# A-Main.net
KiCad netlist of a schematic drawn in Altium Designer
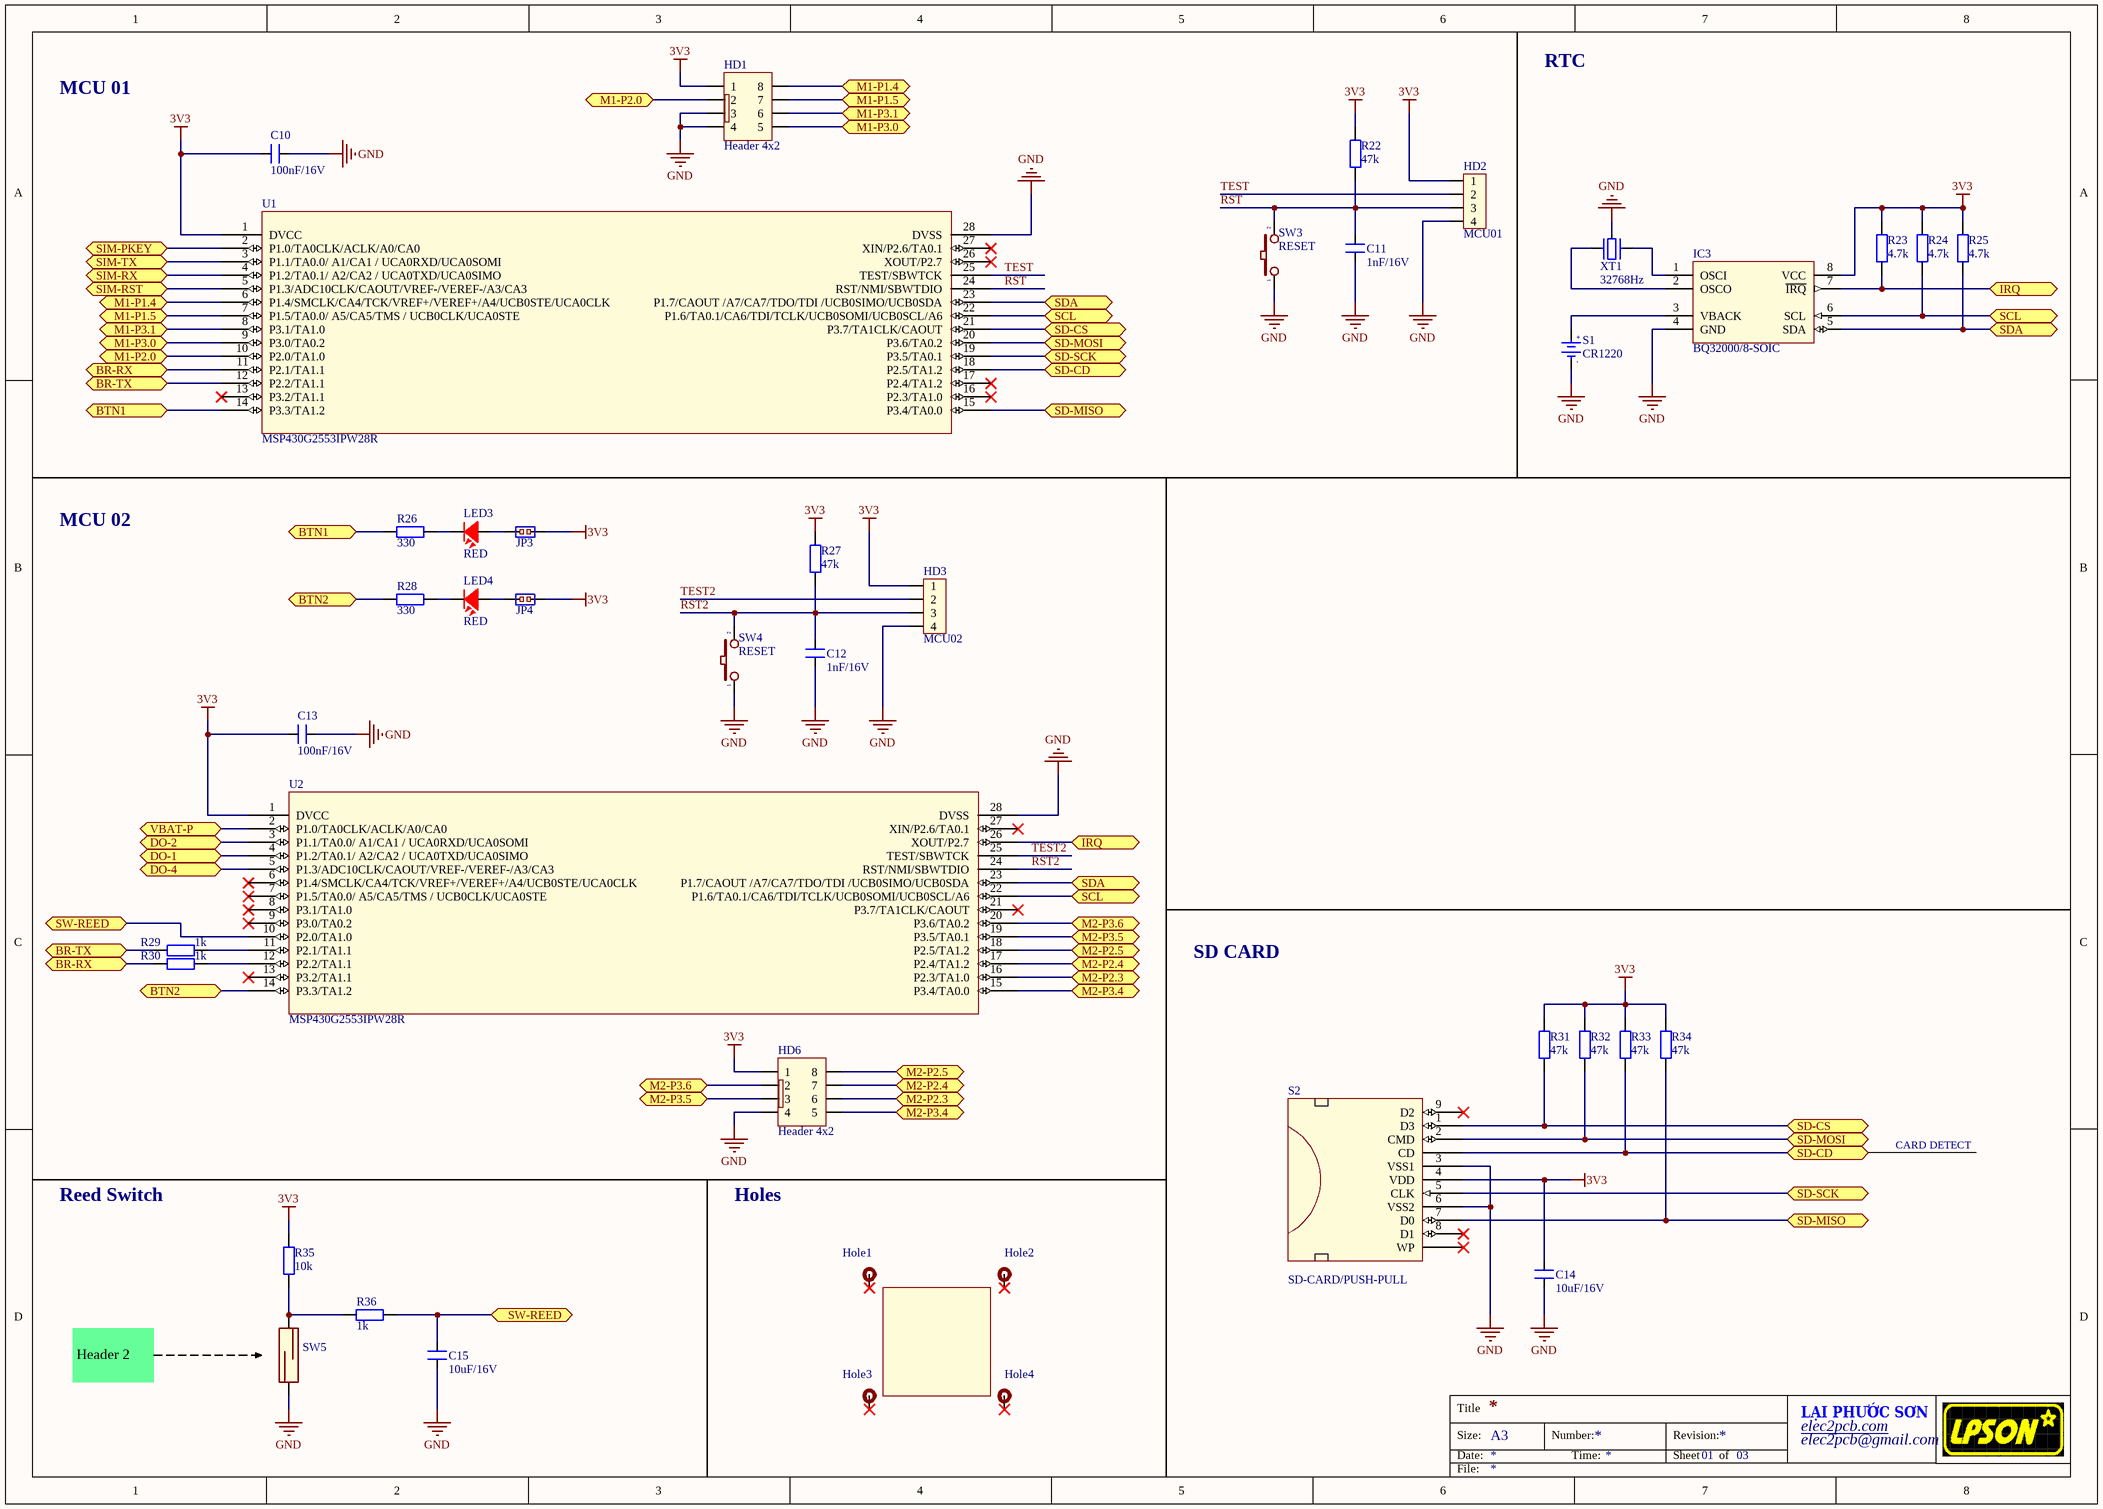
[diagram p0: A-Main.SchDoc]

(export (version "E")
  (design (tool "Eeschema 10.0.6"))
  (components
    (comp (ref "C10")
      (value "100nF/16V")
      (footprint "C0805-2012")
      (description "CAP CER 0.1UF 16V X7R 0805")
      (fields
        (field (name "MANUFACTURER") "Kemet")
        (field (name "MANUFACTURER PART NUMBER") "C0805C104K4RACTU")
      )
      (libsource (lib "Tran Tuan") (part "CAP-CER/100nF/16V/X7R/0805"))
    )
    (comp (ref "C11")
      (value "1nF/16V")
      (footprint "C0603-1608")
      (description "CAP CER 1000PF 16V X7R 0603")
      (fields
        (field (name "MANUFACTURER") "AVX Corporation")
        (field (name "MANUFACTURER PART NUMBER") "0603YC102KAT2A")
      )
      (libsource (lib "Tran Tuan") (part "CAP-CER/1nF/16V/X7R/0603"))
    )
    (comp (ref "C12")
      (value "1nF/16V")
      (footprint "C0603-1608")
      (description "CAP CER 1000PF 16V X7R 0603")
      (fields
        (field (name "MANUFACTURER") "AVX Corporation")
        (field (name "MANUFACTURER PART NUMBER") "0603YC102KAT2A")
      )
      (libsource (lib "Tran Tuan") (part "CAP-CER/1nF/16V/X7R/0603"))
    )
    (comp (ref "C13")
      (value "100nF/16V")
      (footprint "C0805-2012")
      (description "CAP CER 0.1UF 16V X7R 0805")
      (fields
        (field (name "MANUFACTURER") "Kemet")
        (field (name "MANUFACTURER PART NUMBER") "C0805C104K4RACTU")
      )
      (libsource (lib "Tran Tuan") (part "CAP-CER/100nF/16V/X7R/0805"))
    )
    (comp (ref "C14")
      (value "10uF/16V")
      (footprint "C0805-2012")
      (description "CAP CER 10UF 16V X5R 0805")
      (fields
        (field (name "MANUFACTURER") "Murata Electronics North America")
        (field (name "MANUFACTURER PART NUMBER") "GRM21BR61C106KE15L")
      )
      (libsource (lib "Tran Tuan") (part "CAP-CER/10UF/16V/X5R/0805"))
    )
    (comp (ref "C15")
      (value "10uF/16V")
      (footprint "C0805-2012")
      (description "CAP CER 10UF 16V X5R 0805")
      (fields
        (field (name "MANUFACTURER") "Murata Electronics North America")
        (field (name "MANUFACTURER PART NUMBER") "GRM21BR61C106KE15L")
      )
      (libsource (lib "Tran Tuan") (part "CAP-CER/10UF/16V/X5R/0805"))
    )
    (comp (ref "HD1")
      (value "Header 4x2")
      (footprint "HeaderSP_4x2")
      (description "HEADER, 4X2, 2.54MM, MALE")
      (libsource (lib "Tran Tuan") (part "HED-4X2/MALE/2.54MM-B"))
    )
    (comp (ref "HD2")
      (value "MCU01")
      (footprint "Header_4")
      (description "Header 4")
      (libsource (lib "Tran Tuan") (part "Hed4"))
    )
    (comp (ref "HD3")
      (value "MCU02")
      (footprint "Header_4")
      (description "Header 4")
      (libsource (lib "Tran Tuan") (part "Hed4"))
    )
    (comp (ref "HD6")
      (value "Header 4x2")
      (footprint "HeaderSP_4x2")
      (description "HEADER, 4X2, 2.54MM, MALE")
      (libsource (lib "Tran Tuan") (part "HED-4X2/MALE/2.54MM-B"))
    )
    (comp (ref "Hole1")
      (value "Pad Big")
      (footprint "Screw 3.0")
      (libsource (lib "Tran Tuan") (part "Pad_Big"))
    )
    (comp (ref "Hole2")
      (value "Pad Big")
      (footprint "Screw 3.0")
      (libsource (lib "Tran Tuan") (part "Pad_Big"))
    )
    (comp (ref "Hole3")
      (value "Pad Big")
      (footprint "Screw 3.0")
      (libsource (lib "Tran Tuan") (part "Pad_Big"))
    )
    (comp (ref "Hole4")
      (value "Pad Big")
      (footprint "Screw 3.0")
      (libsource (lib "Tran Tuan") (part "Pad_Big"))
    )
    (comp (ref "IC3")
      (value "BQ32000/8-SOIC")
      (footprint "RTC-BQ32000")
      (description "IC RTC CLK/CALENDAR I2C 8-SOIC")
      (fields
        (field (name "MANUFACTURER") "Texas Instruments")
        (field (name "MANUFACTURER PART NUMBER") "BQ32000DR")
      )
      (libsource (lib "Tran Tuan") (part "BQ32000/8-SOIC"))
    )
    (comp (ref "JP3")
      (value "JP2-ShortingJumper")
      (footprint "Header_2")
      (description "2.54mm 2-Pin Shorting Jumper")
      (libsource (lib "Tran Tuan") (part "JP2-ShortingJumper"))
    )
    (comp (ref "JP4")
      (value "JP2-ShortingJumper")
      (footprint "Header_2")
      (description "2.54mm 2-Pin Shorting Jumper")
      (libsource (lib "Tran Tuan") (part "JP2-ShortingJumper"))
    )
    (comp (ref "LED3")
      (value "RED")
      (footprint "Led 0805R")
      (description "LED RED CLEAR 0805 SMD")
      (fields
        (field (name "MANUFACTURER") "Lite-On Inc.")
        (field (name "MANUFACTURER PART NUMBER") "LTST-C171KRKT")
      )
      (libsource (lib "Tran Tuan") (part "LED-RED/CLEAR/0805"))
    )
    (comp (ref "LED4")
      (value "RED")
      (footprint "Led 0805R")
      (description "LED RED CLEAR 0805 SMD")
      (fields
        (field (name "MANUFACTURER") "Lite-On Inc.")
        (field (name "MANUFACTURER PART NUMBER") "LTST-C171KRKT")
      )
      (libsource (lib "Tran Tuan") (part "LED-RED/CLEAR/0805"))
    )
    (comp (ref "R22")
      (value "~")
      (footprint "RESC2012(0805)")
      (description "RES SMD 47K OHM 5% 1/8W 0805")
      (fields
        (field (name "MANUFACTURER") "Yageo")
        (field (name "MANUFACTURER PART NUMBER") "RC0805JR-0747KL")
        (field (name "RESISTANCE (OHMS)") "47k")
      )
      (libsource (lib "") (part "RES-0805/±5%_1"))
    )
    (comp (ref "R23")
      (value "~")
      (footprint "RESC2012(0805)")
      (description "RES SMD 4.7K OHM 5% 1/8W 0805")
      (fields
        (field (name "MANUFACTURER") "Yageo")
        (field (name "MANUFACTURER PART NUMBER") "RC0805JR-074K7L")
        (field (name "RESISTANCE (OHMS)") "4.7k")
      )
      (libsource (lib "") (part "RES-0805/±5%_1"))
    )
    (comp (ref "R24")
      (value "~")
      (footprint "RESC2012(0805)")
      (description "RES SMD 4.7K OHM 5% 1/8W 0805")
      (fields
        (field (name "MANUFACTURER") "Yageo")
        (field (name "MANUFACTURER PART NUMBER") "RC0805JR-074K7L")
        (field (name "RESISTANCE (OHMS)") "4.7k")
      )
      (libsource (lib "") (part "RES-0805/±5%_1"))
    )
    (comp (ref "R25")
      (value "~")
      (footprint "RESC2012(0805)")
      (description "RES SMD 4.7K OHM 5% 1/8W 0805")
      (fields
        (field (name "MANUFACTURER") "Yageo")
        (field (name "MANUFACTURER PART NUMBER") "RC0805JR-074K7L")
        (field (name "RESISTANCE (OHMS)") "4.7k")
      )
      (libsource (lib "") (part "RES-0805/±5%_1"))
    )
    (comp (ref "R26")
      (value "~")
      (footprint "RESC2012(0805)")
      (description "RES SMD 330 OHM 5% 1/8W 0805")
      (fields
        (field (name "MANUFACTURER") "Yageo")
        (field (name "MANUFACTURER PART NUMBER") "RC0805JR-07330RL")
        (field (name "RESISTANCE (OHMS)") "330")
      )
      (libsource (lib "Tran Tuan") (part "RES-0805/±5%"))
    )
    (comp (ref "R27")
      (value "~")
      (footprint "RESC2012(0805)")
      (description "RES SMD 47K OHM 5% 1/8W 0805")
      (fields
        (field (name "MANUFACTURER") "Yageo")
        (field (name "MANUFACTURER PART NUMBER") "RC0805JR-0747KL")
        (field (name "RESISTANCE (OHMS)") "47k")
      )
      (libsource (lib "") (part "RES-0805/±5%_1"))
    )
    (comp (ref "R28")
      (value "~")
      (footprint "RESC2012(0805)")
      (description "RES SMD 330 OHM 5% 1/8W 0805")
      (fields
        (field (name "MANUFACTURER") "Yageo")
        (field (name "MANUFACTURER PART NUMBER") "RC0805JR-07330RL")
        (field (name "RESISTANCE (OHMS)") "330")
      )
      (libsource (lib "Tran Tuan") (part "RES-0805/±5%"))
    )
    (comp (ref "R29")
      (value "~")
      (footprint "RESC2012(0805)")
      (description "RES SMD 1K OHM 5% 1/8W 0805")
      (fields
        (field (name "MANUFACTURER") "Yageo")
        (field (name "MANUFACTURER PART NUMBER") "RC0805JR-071KL")
        (field (name "RESISTANCE (OHMS)") "1k")
      )
      (libsource (lib "Tran Tuan") (part "RES-0805/±5%"))
    )
    (comp (ref "R30")
      (value "~")
      (footprint "RESC2012(0805)")
      (description "RES SMD 1K OHM 5% 1/8W 0805")
      (fields
        (field (name "MANUFACTURER") "Yageo")
        (field (name "MANUFACTURER PART NUMBER") "RC0805JR-071KL")
        (field (name "RESISTANCE (OHMS)") "1k")
      )
      (libsource (lib "Tran Tuan") (part "RES-0805/±5%"))
    )
    (comp (ref "R31")
      (value "~")
      (footprint "RESC2012(0805)")
      (description "RES SMD 47K OHM 5% 1/8W 0805")
      (fields
        (field (name "MANUFACTURER") "Yageo")
        (field (name "MANUFACTURER PART NUMBER") "RC0805JR-0747KL")
        (field (name "RESISTANCE (OHMS)") "47k")
      )
      (libsource (lib "") (part "RES-0805/±5%_1"))
    )
    (comp (ref "R32")
      (value "~")
      (footprint "RESC2012(0805)")
      (description "RES SMD 47K OHM 5% 1/8W 0805")
      (fields
        (field (name "MANUFACTURER") "Yageo")
        (field (name "MANUFACTURER PART NUMBER") "RC0805JR-0747KL")
        (field (name "RESISTANCE (OHMS)") "47k")
      )
      (libsource (lib "") (part "RES-0805/±5%_1"))
    )
    (comp (ref "R33")
      (value "~")
      (footprint "RESC2012(0805)")
      (description "RES SMD 47K OHM 5% 1/8W 0805")
      (fields
        (field (name "MANUFACTURER") "Yageo")
        (field (name "MANUFACTURER PART NUMBER") "RC0805JR-0747KL")
        (field (name "RESISTANCE (OHMS)") "47k")
      )
      (libsource (lib "") (part "RES-0805/±5%_1"))
    )
    (comp (ref "R34")
      (value "~")
      (footprint "RESC2012(0805)")
      (description "RES SMD 47K OHM 5% 1/8W 0805")
      (fields
        (field (name "MANUFACTURER") "Yageo")
        (field (name "MANUFACTURER PART NUMBER") "RC0805JR-0747KL")
        (field (name "RESISTANCE (OHMS)") "47k")
      )
      (libsource (lib "") (part "RES-0805/±5%_1"))
    )
    (comp (ref "R35")
      (value "~")
      (footprint "RESC2012(0805)")
      (description "RES SMD 10K OHM 5% 1/8W 0805")
      (fields
        (field (name "MANUFACTURER") "Yageo")
        (field (name "MANUFACTURER PART NUMBER") "RC0805JR-0710KL")
        (field (name "RESISTANCE (OHMS)") "10k")
      )
      (libsource (lib "") (part "RES-0805/±5%_2"))
    )
    (comp (ref "R36")
      (value "~")
      (footprint "RESC2012(0805)")
      (description "RES SMD 1K OHM 5% 1/8W 0805")
      (fields
        (field (name "MANUFACTURER") "Yageo")
        (field (name "MANUFACTURER PART NUMBER") "RC0805JR-071KL")
        (field (name "RESISTANCE (OHMS)") "1k")
      )
      (libsource (lib "Tran Tuan") (part "RES-0805/±5%"))
    )
    (comp (ref "S1")
      (value "CR1220")
      (footprint "Socket-PIN-BC501SM-TR")
      (description "CR1220 Battery Holder SMD")
      (fields (field (name "Comment") "BAT-HOLDER/CR1220/TME"))
      (libsource (lib "Tran Tuan") (part "BAT-HOLDER/CR1220/TME"))
    )
    (comp (ref "S2")
      (value "SD-CARD/PUSH-PULL")
      (footprint "SD-CARD")
      (description "CONN SD CARD PUSH-PUSH R/A SMD")
      (fields
        (field (name "MANUFACTURER") "Amphenol Commercial Products")
        (field (name "MANUFACTURER PART NUMBER") "101-00313-68-02")
      )
      (libsource (lib "Tran Tuan") (part "SD-CARD/PUSH-PULL"))
    )
    (comp (ref "SW3")
      (value "RESET")
      (footprint "BTN-EVQ-11A04M")
      (description "SWITCH TACTILE SPST-NO 0.02A 15V")
      (fields
        (field (name "MANUFACTURER") "Panasonic Electronic Components")
        (field (name "MANUFACTURER PART NUMBER") "EVQ-11A04M")
      )
      (libsource (lib "Tran Tuan") (part "SW2-PUSH/SPST/NO"))
    )
    (comp (ref "SW4")
      (value "RESET")
      (footprint "BTN-EVQ-11A04M")
      (description "SWITCH TACTILE SPST-NO 0.02A 15V")
      (fields
        (field (name "MANUFACTURER") "Panasonic Electronic Components")
        (field (name "MANUFACTURER PART NUMBER") "EVQ-11A04M")
      )
      (libsource (lib "Tran Tuan") (part "SW2-PUSH/SPST/NO"))
    )
    (comp (ref "SW5")
      (value "SW-REED/SPST/NO/350mA")
      (footprint "SWITCH-SDSM")
      (description "SWITCH REED SPST-NO 350MA 140V")
      (fields
        (field (name "MANUFACTURER") "Littelfuse Inc.")
        (field (name "MANUFACTURER PART NUMBER") "MDSM-4R-12-18")
      )
      (libsource (lib "Tran Tuan") (part "SW-REED/SPST/NO/350mA"))
    )
    (comp (ref "U1")
      (value "MSP430G2553IPW28R")
      (footprint "MSP430G2253IPW28R")
      (description "IC MCU 16BIT 16KB FLASH 28TSSOP")
      (fields (field (name "MANUFACTURER") "Texas Instruments"))
      (libsource (lib "Tran Tuan") (part "MSP430G2553IPW28R"))
    )
    (comp (ref "U2")
      (value "MSP430G2553IPW28R")
      (footprint "MSP430G2253IPW28R")
      (description "IC MCU 16BIT 16KB FLASH 28TSSOP")
      (fields (field (name "MANUFACTURER") "Texas Instruments"))
      (libsource (lib "Tran Tuan") (part "MSP430G2553IPW28R"))
    )
    (comp (ref "XT1")
      (value "32768Hz")
      (footprint "CR_32768")
      (description "CRYSTAL 32.7680KHZ 12.5PF T/H")
      (fields
        (field (name "MANUFACTURER") "Citizen Finedevice Co Ltd")
        (field (name "MANUFACTURER PART NUMBER") "CFS206-32.768KDZF-UB")
      )
      (libsource (lib "Tran Tuan") (part "XT-32768HZ/RADIAL"))
    )
  )
  (nets
    (net (code "1") (name "/BR-RX") (class "Default")
      (node (ref "R30") (pin "2") (pinfunction "2_2") (pintype "passive"))
      (node (ref "U1") (pin "11") (pinfunction "P2.1/TA1.1_11") (pintype "bidirectional"))
    )
    (net (code "2") (name "/BR-TX") (class "Default")
      (node (ref "R29") (pin "2") (pinfunction "2_2") (pintype "passive"))
      (node (ref "U1") (pin "12") (pinfunction "P2.2/TA1.1_12") (pintype "bidirectional"))
    )
    (net (code "3") (name "/BTN1") (class "Default")
      (node (ref "R26") (pin "2") (pinfunction "2_2") (pintype "passive"))
      (node (ref "U1") (pin "14") (pinfunction "P3.3/TA1.2_14") (pintype "bidirectional"))
    )
    (net (code "4") (name "/BTN2") (class "Default")
      (node (ref "R28") (pin "2") (pinfunction "2_2") (pintype "passive"))
      (node (ref "U2") (pin "14") (pinfunction "P3.3/TA1.2_14") (pintype "bidirectional"))
    )
    (net (code "5") (name "/DO-1") (class "Default")
      (node (ref "U2") (pin "4") (pinfunction "P1.2/TA0.1/_A2/CA2_/_UCA0TXD/UCA0SIMO_4") (pintype "bidirectional"))
    )
    (net (code "6") (name "/DO-2") (class "Default")
      (node (ref "U2") (pin "3") (pinfunction "P1.1/TA0.0/_A1/CA1_/_UCA0RXD/UCA0SOMI_3") (pintype "bidirectional"))
    )
    (net (code "7") (name "/DO-4") (class "Default")
      (node (ref "U2") (pin "5") (pinfunction "P1.3/ADC10CLK/CAOUT/VREF-/VEREF-/A3/CA3_5") (pintype "bidirectional"))
    )
    (net (code "8") (name "/IRQ") (class "Default")
      (node (ref "IC3") (pin "7") (pinfunction "~{IRQ}_7") (pintype "output"))
      (node (ref "R23") (pin "1") (pinfunction "1_1") (pintype "passive"))
      (node (ref "U2") (pin "26") (pinfunction "XOUT/P2.7_26") (pintype "bidirectional"))
    )
    (net (code "9") (name "/M1-P1.4") (class "Default")
      (node (ref "HD1") (pin "8") (pinfunction "8_8") (pintype "passive"))
      (node (ref "U1") (pin "6") (pinfunction "P1.4/SMCLK/CA4/TCK/VREF+/VEREF+/A4/UCB0STE/UCA0CLK_6") (pintype "bidirectional"))
    )
    (net (code "10") (name "/M1-P1.5") (class "Default")
      (node (ref "HD1") (pin "7") (pinfunction "7_7") (pintype "passive"))
      (node (ref "U1") (pin "7") (pinfunction "P1.5/TA0.0/_A5/CA5/TMS_/_UCB0CLK/UCA0STE_7") (pintype "bidirectional"))
    )
    (net (code "11") (name "/M1-P2.0") (class "Default")
      (node (ref "HD1") (pin "2") (pinfunction "2_2") (pintype "passive"))
      (node (ref "U1") (pin "10") (pinfunction "P2.0/TA1.0_10") (pintype "bidirectional"))
    )
    (net (code "12") (name "/M1-P3.0") (class "Default")
      (node (ref "HD1") (pin "5") (pinfunction "5_5") (pintype "passive"))
      (node (ref "U1") (pin "9") (pinfunction "P3.0/TA0.2_9") (pintype "bidirectional"))
    )
    (net (code "13") (name "/M1-P3.1") (class "Default")
      (node (ref "HD1") (pin "6") (pinfunction "6_6") (pintype "passive"))
      (node (ref "U1") (pin "8") (pinfunction "P3.1/TA1.0_8") (pintype "bidirectional"))
    )
    (net (code "14") (name "/M2-P2.3") (class "Default")
      (node (ref "HD6") (pin "6") (pinfunction "6_6") (pintype "passive"))
      (node (ref "U2") (pin "16") (pinfunction "P2.3/TA1.0_16") (pintype "bidirectional"))
    )
    (net (code "15") (name "/M2-P2.4") (class "Default")
      (node (ref "HD6") (pin "7") (pinfunction "7_7") (pintype "passive"))
      (node (ref "U2") (pin "17") (pinfunction "P2.4/TA1.2_17") (pintype "bidirectional"))
    )
    (net (code "16") (name "/M2-P2.5") (class "Default")
      (node (ref "HD6") (pin "8") (pinfunction "8_8") (pintype "passive"))
      (node (ref "U2") (pin "18") (pinfunction "P2.5/TA1.2_18") (pintype "bidirectional"))
    )
    (net (code "17") (name "/M2-P3.4") (class "Default")
      (node (ref "HD6") (pin "5") (pinfunction "5_5") (pintype "passive"))
      (node (ref "U2") (pin "15") (pinfunction "P3.4/TA0.0_15") (pintype "bidirectional"))
    )
    (net (code "18") (name "/M2-P3.5") (class "Default")
      (node (ref "HD6") (pin "3") (pinfunction "3_3") (pintype "passive"))
      (node (ref "U2") (pin "19") (pinfunction "P3.5/TA0.1_19") (pintype "bidirectional"))
    )
    (net (code "19") (name "/M2-P3.6") (class "Default")
      (node (ref "HD6") (pin "2") (pinfunction "2_2") (pintype "passive"))
      (node (ref "U2") (pin "20") (pinfunction "P3.6/TA0.2_20") (pintype "bidirectional"))
    )
    (net (code "20") (name "/RST") (class "Default")
      (node (ref "C11") (pin "1") (pinfunction "1_1") (pintype "passive"))
      (node (ref "HD2") (pin "3") (pinfunction "3_3") (pintype "passive"))
      (node (ref "R22") (pin "1") (pinfunction "1_1") (pintype "passive"))
      (node (ref "SW3") (pin "2") (pinfunction "2_2") (pintype "passive"))
      (node (ref "U1") (pin "24") (pinfunction "RST/NMI/SBWTDIO_24") (pintype "passive"))
    )
    (net (code "21") (name "/RST2") (class "Default")
      (node (ref "C12") (pin "1") (pinfunction "1_1") (pintype "passive"))
      (node (ref "HD3") (pin "3") (pinfunction "3_3") (pintype "passive"))
      (node (ref "R27") (pin "1") (pinfunction "1_1") (pintype "passive"))
      (node (ref "SW4") (pin "2") (pinfunction "2_2") (pintype "passive"))
      (node (ref "U2") (pin "24") (pinfunction "RST/NMI/SBWTDIO_24") (pintype "passive"))
    )
    (net (code "22") (name "/SCL") (class "Default")
      (node (ref "IC3") (pin "6") (pinfunction "SCL_6") (pintype "input"))
      (node (ref "R24") (pin "1") (pinfunction "1_1") (pintype "passive"))
      (node (ref "U1") (pin "22") (pinfunction "P1.6/TA0.1/CA6/TDI/TCLK/UCB0SOMI/UCB0SCL/A6_22") (pintype "bidirectional"))
      (node (ref "U2") (pin "22") (pinfunction "P1.6/TA0.1/CA6/TDI/TCLK/UCB0SOMI/UCB0SCL/A6_22") (pintype "bidirectional"))
    )
    (net (code "23") (name "/SD-CD") (class "Default")
      (node (ref "R33") (pin "1") (pinfunction "1_1") (pintype "passive"))
      (node (ref "S2") (pin "CD") (pinfunction "CD_CD") (pintype "passive"))
      (node (ref "U1") (pin "18") (pinfunction "P2.5/TA1.2_18") (pintype "bidirectional"))
    )
    (net (code "24") (name "/SD-CS") (class "Default")
      (node (ref "R31") (pin "1") (pinfunction "1_1") (pintype "passive"))
      (node (ref "S2") (pin "1") (pinfunction "D3_1") (pintype "bidirectional"))
      (node (ref "U1") (pin "21") (pinfunction "P3.7/TA1CLK/CAOUT_21") (pintype "bidirectional"))
    )
    (net (code "25") (name "/SD-MISO") (class "Default")
      (node (ref "R34") (pin "1") (pinfunction "1_1") (pintype "passive"))
      (node (ref "S2") (pin "7") (pinfunction "D0_7") (pintype "bidirectional"))
      (node (ref "U1") (pin "15") (pinfunction "P3.4/TA0.0_15") (pintype "bidirectional"))
    )
    (net (code "26") (name "/SD-MOSI") (class "Default")
      (node (ref "R32") (pin "1") (pinfunction "1_1") (pintype "passive"))
      (node (ref "S2") (pin "2") (pinfunction "CMD_2") (pintype "bidirectional"))
      (node (ref "U1") (pin "20") (pinfunction "P3.6/TA0.2_20") (pintype "bidirectional"))
    )
    (net (code "27") (name "/SD-SCK") (class "Default")
      (node (ref "S2") (pin "5") (pinfunction "CLK_5") (pintype "input"))
      (node (ref "U1") (pin "19") (pinfunction "P3.5/TA0.1_19") (pintype "bidirectional"))
    )
    (net (code "28") (name "/SDA") (class "Default")
      (node (ref "IC3") (pin "5") (pinfunction "SDA_5") (pintype "bidirectional"))
      (node (ref "R25") (pin "1") (pinfunction "1_1") (pintype "passive"))
      (node (ref "U1") (pin "23") (pinfunction "P1.7/CAOUT_/A7/CA7/TDO/TDI_/UCB0SIMO/UCB0SDA_23") (pintype "bidirectional"))
      (node (ref "U2") (pin "23") (pinfunction "P1.7/CAOUT_/A7/CA7/TDO/TDI_/UCB0SIMO/UCB0SDA_23") (pintype "bidirectional"))
    )
    (net (code "29") (name "/SIM-PKEY") (class "Default")
      (node (ref "U1") (pin "2") (pinfunction "P1.0/TA0CLK/ACLK/A0/CA0_2") (pintype "bidirectional"))
    )
    (net (code "30") (name "/SIM-RST") (class "Default")
      (node (ref "U1") (pin "5") (pinfunction "P1.3/ADC10CLK/CAOUT/VREF-/VEREF-/A3/CA3_5") (pintype "bidirectional"))
    )
    (net (code "31") (name "/SIM-RX") (class "Default")
      (node (ref "U1") (pin "4") (pinfunction "P1.2/TA0.1/_A2/CA2_/_UCA0TXD/UCA0SIMO_4") (pintype "bidirectional"))
    )
    (net (code "32") (name "/SIM-TX") (class "Default")
      (node (ref "U1") (pin "3") (pinfunction "P1.1/TA0.0/_A1/CA1_/_UCA0RXD/UCA0SOMI_3") (pintype "bidirectional"))
    )
    (net (code "33") (name "/SW-REED") (class "Default")
      (node (ref "C15") (pin "1") (pinfunction "1_1") (pintype "passive"))
      (node (ref "R36") (pin "1") (pinfunction "1_1") (pintype "passive"))
      (node (ref "U2") (pin "10") (pinfunction "P2.0/TA1.0_10") (pintype "bidirectional"))
    )
    (net (code "34") (name "/TEST") (class "Default")
      (node (ref "HD2") (pin "2") (pinfunction "2_2") (pintype "passive"))
      (node (ref "U1") (pin "25") (pinfunction "TEST/SBWTCK_25") (pintype "passive"))
    )
    (net (code "35") (name "/TEST2") (class "Default")
      (node (ref "HD3") (pin "2") (pinfunction "2_2") (pintype "passive"))
      (node (ref "U2") (pin "25") (pinfunction "TEST/SBWTCK_25") (pintype "passive"))
    )
    (net (code "36") (name "/VBAT-P") (class "Default")
      (node (ref "U2") (pin "2") (pinfunction "P1.0/TA0CLK/ACLK/A0/CA0_2") (pintype "bidirectional"))
    )
    (net (code "37") (name "3V3") (class "Default")
      (node (ref "C10") (pin "1") (pinfunction "1_1") (pintype "passive"))
      (node (ref "C13") (pin "1") (pinfunction "1_1") (pintype "passive"))
      (node (ref "C14") (pin "1") (pinfunction "1_1") (pintype "passive"))
      (node (ref "HD1") (pin "1") (pinfunction "1_1") (pintype "passive"))
      (node (ref "HD2") (pin "1") (pinfunction "1_1") (pintype "passive"))
      (node (ref "HD3") (pin "1") (pinfunction "1_1") (pintype "passive"))
      (node (ref "HD6") (pin "1") (pinfunction "1_1") (pintype "passive"))
      (node (ref "IC3") (pin "8") (pinfunction "VCC_8") (pintype "power_in"))
      (node (ref "JP3") (pin "2") (pinfunction "2_2") (pintype "passive"))
      (node (ref "JP4") (pin "2") (pinfunction "2_2") (pintype "passive"))
      (node (ref "R22") (pin "2") (pinfunction "2_2") (pintype "passive"))
      (node (ref "R23") (pin "2") (pinfunction "2_2") (pintype "passive"))
      (node (ref "R24") (pin "2") (pinfunction "2_2") (pintype "passive"))
      (node (ref "R25") (pin "2") (pinfunction "2_2") (pintype "passive"))
      (node (ref "R27") (pin "2") (pinfunction "2_2") (pintype "passive"))
      (node (ref "R31") (pin "2") (pinfunction "2_2") (pintype "passive"))
      (node (ref "R32") (pin "2") (pinfunction "2_2") (pintype "passive"))
      (node (ref "R33") (pin "2") (pinfunction "2_2") (pintype "passive"))
      (node (ref "R34") (pin "2") (pinfunction "2_2") (pintype "passive"))
      (node (ref "R35") (pin "1") (pinfunction "1_1") (pintype "passive"))
      (node (ref "S2") (pin "4") (pinfunction "VDD_4") (pintype "power_in"))
      (node (ref "U1") (pin "1") (pinfunction "DVCC_1") (pintype "power_in"))
      (node (ref "U2") (pin "1") (pinfunction "DVCC_1") (pintype "power_in"))
    )
    (net (code "38") (name "GND") (class "Default")
      (node (ref "C10") (pin "2") (pinfunction "2_2") (pintype "passive"))
      (node (ref "C11") (pin "2") (pinfunction "2_2") (pintype "passive"))
      (node (ref "C12") (pin "2") (pinfunction "2_2") (pintype "passive"))
      (node (ref "C13") (pin "2") (pinfunction "2_2") (pintype "passive"))
      (node (ref "C14") (pin "2") (pinfunction "2_2") (pintype "passive"))
      (node (ref "C15") (pin "2") (pinfunction "2_2") (pintype "passive"))
      (node (ref "HD1") (pin "3") (pinfunction "3_3") (pintype "passive"))
      (node (ref "HD1") (pin "4") (pinfunction "4_4") (pintype "passive"))
      (node (ref "HD2") (pin "4") (pinfunction "4_4") (pintype "passive"))
      (node (ref "HD3") (pin "4") (pinfunction "4_4") (pintype "passive"))
      (node (ref "HD6") (pin "4") (pinfunction "4_4") (pintype "passive"))
      (node (ref "IC3") (pin "4") (pinfunction "GND_4") (pintype "power_in"))
      (node (ref "S1") (pin "2") (pinfunction "GND_2") (pintype "passive"))
      (node (ref "S2") (pin "3") (pinfunction "VSS1_3") (pintype "power_in"))
      (node (ref "S2") (pin "6") (pinfunction "VSS2_6") (pintype "power_in"))
      (node (ref "SW3") (pin "1") (pinfunction "1_1") (pintype "passive"))
      (node (ref "SW4") (pin "1") (pinfunction "1_1") (pintype "passive"))
      (node (ref "SW5") (pin "1") (pinfunction "1_1") (pintype "passive"))
      (node (ref "U1") (pin "28") (pinfunction "DVSS_28") (pintype "passive"))
      (node (ref "U2") (pin "28") (pinfunction "DVSS_28") (pintype "passive"))
      (node (ref "XT1") (pin "0") (pinfunction "Case_0") (pintype "passive"))
    )
    (net (code "39") (name "Net-(IC3-OSCI)") (class "Default")
      (node (ref "IC3") (pin "1") (pinfunction "OSCI_1") (pintype "passive"))
      (node (ref "XT1") (pin "2") (pinfunction "2_2") (pintype "passive"))
    )
    (net (code "40") (name "Net-(IC3-OSCO)") (class "Default")
      (node (ref "IC3") (pin "2") (pinfunction "OSCO_2") (pintype "passive"))
      (node (ref "XT1") (pin "1") (pinfunction "1_1") (pintype "passive"))
    )
    (net (code "41") (name "Net-(IC3-VBACK)") (class "Default")
      (node (ref "IC3") (pin "3") (pinfunction "VBACK_3") (pintype "power_in"))
      (node (ref "S1") (pin "1") (pinfunction "+3V_1") (pintype "passive"))
    )
    (net (code "42") (name "Net-(LED3-A)") (class "Default")
      (node (ref "JP3") (pin "1") (pinfunction "1_1") (pintype "passive"))
      (node (ref "LED3") (pin "1") (pinfunction "A_1") (pintype "passive"))
    )
    (net (code "43") (name "Net-(LED3-K)") (class "Default")
      (node (ref "LED3") (pin "2") (pinfunction "K_2") (pintype "passive"))
      (node (ref "R26") (pin "1") (pinfunction "1_1") (pintype "passive"))
    )
    (net (code "44") (name "Net-(LED4-A)") (class "Default")
      (node (ref "JP4") (pin "1") (pinfunction "1_1") (pintype "passive"))
      (node (ref "LED4") (pin "1") (pinfunction "A_1") (pintype "passive"))
    )
    (net (code "45") (name "Net-(LED4-K)") (class "Default")
      (node (ref "LED4") (pin "2") (pinfunction "K_2") (pintype "passive"))
      (node (ref "R28") (pin "1") (pinfunction "1_1") (pintype "passive"))
    )
    (net (code "46") (name "Net-(R35-Pad2)") (class "Default")
      (node (ref "R35") (pin "2") (pinfunction "2_2") (pintype "passive"))
      (node (ref "R36") (pin "2") (pinfunction "2_2") (pintype "passive"))
      (node (ref "SW5") (pin "2") (pinfunction "2_2") (pintype "passive"))
    )
    (net (code "47") (name "Net-(U2-P2.1{slash}TA1.1)") (class "Default")
      (node (ref "R29") (pin "1") (pinfunction "1_1") (pintype "passive"))
      (node (ref "U2") (pin "11") (pinfunction "P2.1/TA1.1_11") (pintype "bidirectional"))
    )
    (net (code "48") (name "Net-(U2-P2.2{slash}TA1.1)") (class "Default")
      (node (ref "R30") (pin "1") (pinfunction "1_1") (pintype "passive"))
      (node (ref "U2") (pin "12") (pinfunction "P2.2/TA1.1_12") (pintype "bidirectional"))
    )
    (net (code "49") (name "unconnected-(Hole1-Pad1)") (class "Default")
      (node (ref "Hole1") (pin "1") (pinfunction "1_1") (pintype "passive+no_connect"))
    )
    (net (code "50") (name "unconnected-(Hole2-Pad1)") (class "Default")
      (node (ref "Hole2") (pin "1") (pinfunction "1_1") (pintype "passive+no_connect"))
    )
    (net (code "51") (name "unconnected-(Hole3-Pad1)") (class "Default")
      (node (ref "Hole3") (pin "1") (pinfunction "1_1") (pintype "passive+no_connect"))
    )
    (net (code "52") (name "unconnected-(Hole4-Pad1)") (class "Default")
      (node (ref "Hole4") (pin "1") (pinfunction "1_1") (pintype "passive+no_connect"))
    )
    (net (code "53") (name "unconnected-(S2-D1-Pad8)") (class "Default")
      (node (ref "S2") (pin "8") (pinfunction "D1_8") (pintype "bidirectional+no_connect"))
    )
    (net (code "54") (name "unconnected-(S2-D2-Pad9)") (class "Default")
      (node (ref "S2") (pin "9") (pinfunction "D2_9") (pintype "bidirectional+no_connect"))
    )
    (net (code "55") (name "unconnected-(S2-PadWP)") (class "Default")
      (node (ref "S2") (pin "WP") (pinfunction "WP_WP") (pintype "passive+no_connect"))
    )
    (net (code "56") (name "unconnected-(U1-P2.3{slash}TA1.0-Pad16)") (class "Default")
      (node (ref "U1") (pin "16") (pinfunction "P2.3/TA1.0_16") (pintype "bidirectional+no_connect"))
    )
    (net (code "57") (name "unconnected-(U1-P2.4{slash}TA1.2-Pad17)") (class "Default")
      (node (ref "U1") (pin "17") (pinfunction "P2.4/TA1.2_17") (pintype "bidirectional+no_connect"))
    )
    (net (code "58") (name "unconnected-(U1-P3.2{slash}TA1.1-Pad13)") (class "Default")
      (node (ref "U1") (pin "13") (pinfunction "P3.2/TA1.1_13") (pintype "bidirectional+no_connect"))
    )
    (net (code "59") (name "unconnected-(U1-XIN{slash}P2.6{slash}TA0.1-Pad27)") (class "Default")
      (node (ref "U1") (pin "27") (pinfunction "XIN/P2.6/TA0.1_27") (pintype "bidirectional+no_connect"))
    )
    (net (code "60") (name "unconnected-(U1-XOUT{slash}P2.7-Pad26)") (class "Default")
      (node (ref "U1") (pin "26") (pinfunction "XOUT/P2.7_26") (pintype "bidirectional+no_connect"))
    )
    (net (code "61") (name "unconnected-(U2-P1.4{slash}SMCLK{slash}CA4{slash}TCK{slash}VREF+{slash}VEREF+{slash}A4{slash}UCB0STE{slash}UCA0CLK-Pad6)") (class "Default")
      (node (ref "U2") (pin "6") (pinfunction "P1.4/SMCLK/CA4/TCK/VREF+/VEREF+/A4/UCB0STE/UCA0CLK_6") (pintype "bidirectional+no_connect"))
    )
    (net (code "62") (name "unconnected-(U2-P1.5{slash}TA0.0{slash}_A5{slash}CA5{slash}TMS_{slash}_UCB0CLK{slash}UCA0STE-Pad7)") (class "Default")
      (node (ref "U2") (pin "7") (pinfunction "P1.5/TA0.0/_A5/CA5/TMS_/_UCB0CLK/UCA0STE_7") (pintype "bidirectional+no_connect"))
    )
    (net (code "63") (name "unconnected-(U2-P3.0{slash}TA0.2-Pad9)") (class "Default")
      (node (ref "U2") (pin "9") (pinfunction "P3.0/TA0.2_9") (pintype "bidirectional+no_connect"))
    )
    (net (code "64") (name "unconnected-(U2-P3.1{slash}TA1.0-Pad8)") (class "Default")
      (node (ref "U2") (pin "8") (pinfunction "P3.1/TA1.0_8") (pintype "bidirectional+no_connect"))
    )
    (net (code "65") (name "unconnected-(U2-P3.2{slash}TA1.1-Pad13)") (class "Default")
      (node (ref "U2") (pin "13") (pinfunction "P3.2/TA1.1_13") (pintype "bidirectional+no_connect"))
    )
    (net (code "66") (name "unconnected-(U2-P3.7{slash}TA1CLK{slash}CAOUT-Pad21)") (class "Default")
      (node (ref "U2") (pin "21") (pinfunction "P3.7/TA1CLK/CAOUT_21") (pintype "bidirectional+no_connect"))
    )
    (net (code "67") (name "unconnected-(U2-XIN{slash}P2.6{slash}TA0.1-Pad27)") (class "Default")
      (node (ref "U2") (pin "27") (pinfunction "XIN/P2.6/TA0.1_27") (pintype "bidirectional+no_connect"))
    )
  )
)
